# 60V_Ind.net
KiCad netlist of a schematic drawn in Altium Designer
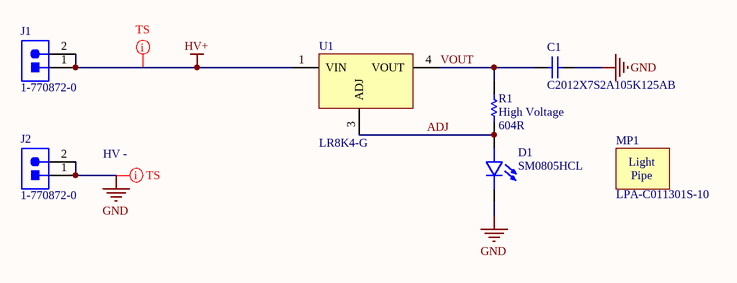
[diagram p0: 60V_Ind.SchDoc]

(export (version "E")
  (design (tool "Eeschema 10.0.6"))
  (components
    (comp (ref "C1")
      (value "C2012X7S2A105K125AB")
      (footprint "CAPC2013X145X20ML20")
      (description "Chip Capacitor, 1 uF, +/- 10%, 100 V, -55 to 125 degC, 0805 (2012 Metric), RoHS, Tape and Reel")
      (fields
        (field (name "PCN PART NUMBER") "MLCCPartNumberChange30/Nov/2012")
        (field (name "MANUFACTURER") "TDK")
      )
      (libsource (lib "60V_Ind") (part "C2012X7S2A105K125AB"))
    )
    (comp (ref "D1")
      (value "SM0805HCL")
      (footprint "LEDC2012X135N_SM0805UGC(Primary)")
      (description "Red 631nm LED Indication - Discrete 1.9V 0805 (2012 Metric)")
      (libsource (lib "60V_Ind") (part "SM0805HCL"))
    )
    (comp (ref "J1")
      (value "1-770872-0")
      (footprint "CON2_1X2_P163_VM")
      (description "Connector Header Through Hole 2 position 0.163\" (4.14mm)")
      (fields (field (name "COPYRIGHT") "Copyright (C) 2018 Accelerated Designs. All rights reserved"))
      (libsource (lib "60V_Ind") (part "1-770872-0"))
    )
    (comp (ref "J2")
      (value "1-770872-0")
      (footprint "CON2_1X2_P163_VM")
      (description "Connector Header Through Hole 2 position 0.163\" (4.14mm)")
      (fields (field (name "COPYRIGHT") "Copyright (C) 2018 Accelerated Designs. All rights reserved"))
      (libsource (lib "60V_Ind") (part "1-770872-0"))
    )
    (comp (ref "MP1")
      (value "LPA-C011301S-10")
      (footprint "LPA-C011301S-10")
      (description "Light Pipe Single Clear Rigid Round with Flat Top, 3mm Board Mount, Press Fit")
      (libsource (lib "60V_Ind") (part "LPA-C011301S-10"))
    )
    (comp (ref "R1")
      (value "KTR10EZPF6040")
      (footprint "RESC2012X06N_HV")
      (fields
        (field (name "MANUFACTURER") "Rohm")
        (field (name "TOLERANCE") "1%")
        (field (name "HIGH VOLTAGE") "High Voltage")
        (field (name "RESISTANCE") "604R")
      )
      (libsource (lib "AERO Parts") (part "KTR10EZPF6040"))
    )
    (comp (ref "U1")
      (value "LR8K4-G")
      (footprint "Microchip_C04-189_MFG")
      (description "Linear Voltage Regulator IC Positive Adjustable 1 Output  10mA TO-252, (D-Pak)")
      (libsource (lib "60V_Ind") (part "LR8K4-G"))
    )
  )
  (nets
    (net (code "1") (name "/ADJ") (class "Default")
      (node (ref "D1") (pin "A") (pinfunction "A_A") (pintype "passive"))
      (node (ref "R1") (pin "1") (pinfunction "1_1") (pintype "passive"))
      (node (ref "U1") (pin "3") (pinfunction "ADJ_3") (pintype "passive"))
    )
    (net (code "2") (name "/VOUT") (class "Default")
      (node (ref "C1") (pin "1") (pinfunction "1_1") (pintype "passive"))
      (node (ref "R1") (pin "2") (pinfunction "2_2") (pintype "passive"))
      (node (ref "U1") (pin "4") (pinfunction "VOUT_4") (pintype "power_in"))
    )
    (net (code "3") (name "GND") (class "Default")
      (node (ref "C1") (pin "2") (pinfunction "2_2") (pintype "passive"))
      (node (ref "D1") (pin "C") (pinfunction "C_C") (pintype "passive"))
      (node (ref "J2") (pin "1") (pinfunction "1_1") (pintype "passive"))
      (node (ref "J2") (pin "2") (pinfunction "2_2") (pintype "passive"))
    )
    (net (code "4") (name "HV+") (class "Default")
      (node (ref "J1") (pin "1") (pinfunction "1_1") (pintype "passive"))
      (node (ref "J1") (pin "2") (pinfunction "2_2") (pintype "passive"))
      (node (ref "U1") (pin "1") (pinfunction "VIN_1") (pintype "power_in"))
    )
  )
)
